# PROC010B_XDS110_Interface_1B.net
KiCad netlist of a schematic drawn in Altium Designer
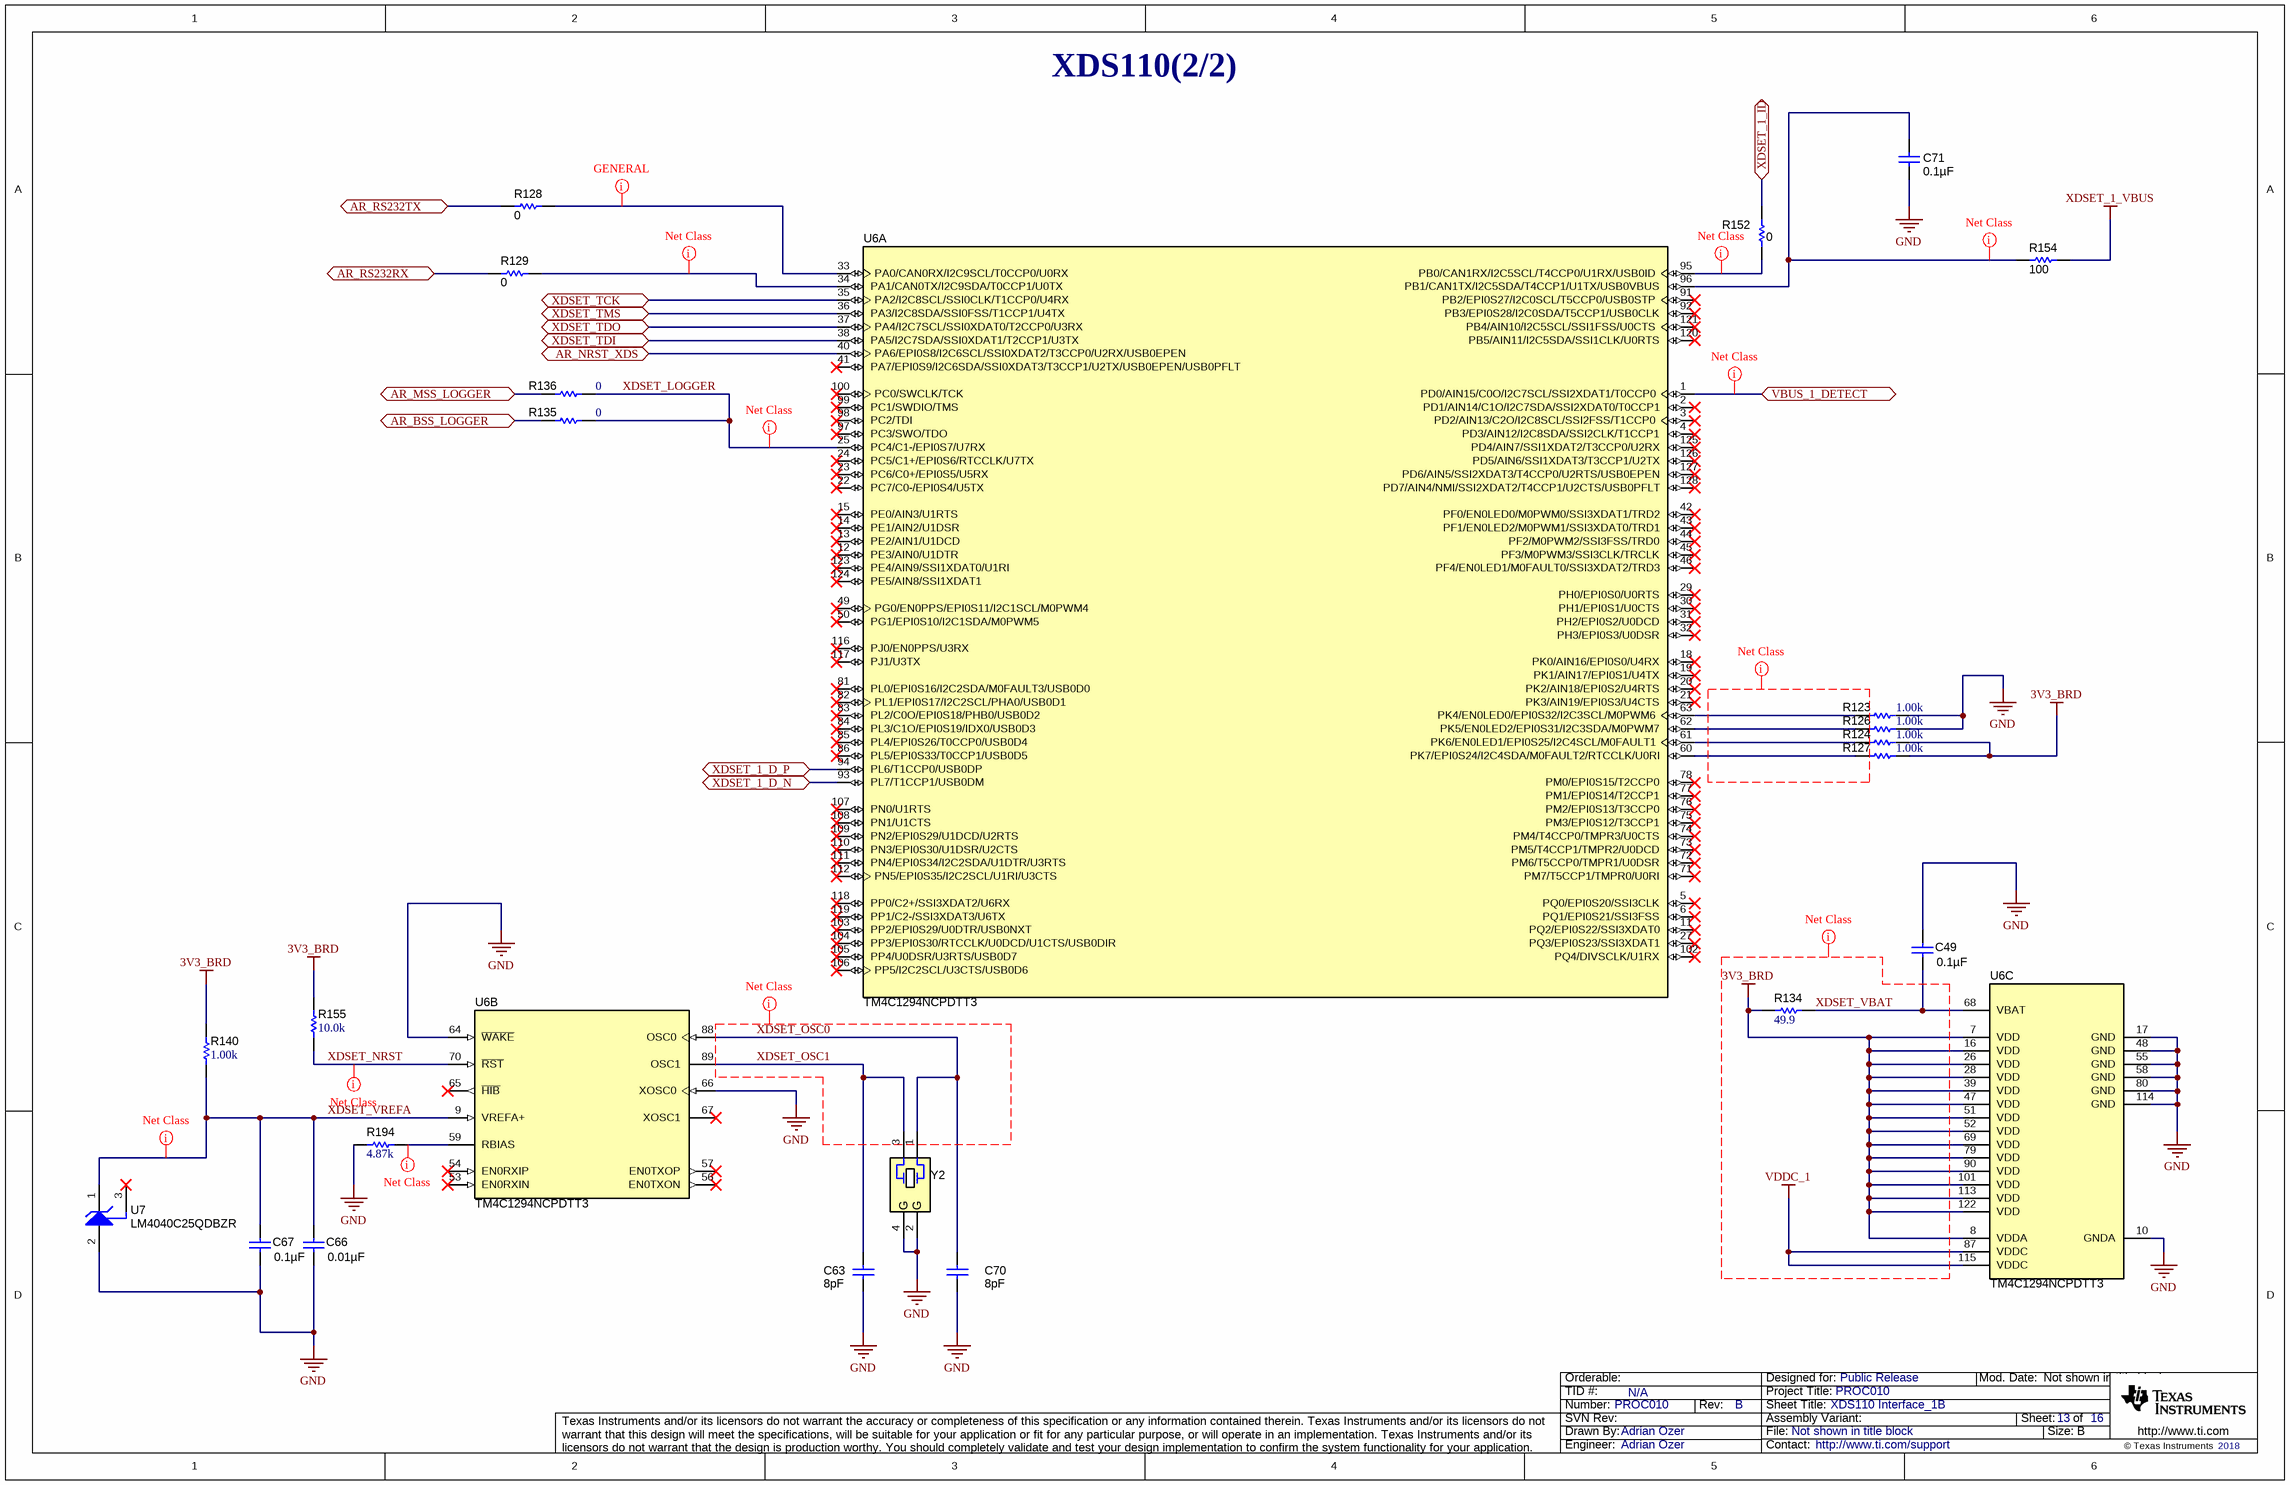
[diagram p0: PROC010B_XDS110 Interface_1B.SchDoc]

(export (version "E")
  (design (tool "Eeschema 10.0.6"))
  (components
    (comp (ref "C49")
      (value "C0402C104K8RACTU")
      (footprint "0402L")
      (description "CAP, CERM, 0.1 µF, 10 V,+/- 10%, X7R, 0402")
      (fields (field (name "MANUFACTURER") "Kemet") (field (name "VALUEDISPLAYED") "0.1µF"))
      (libsource (lib "Altium Vault - TI") (part "CMP-0078241-1"))
    )
    (comp (ref "C63")
      (value "GRM1555C1H8R0DA01D")
      (footprint "0402L")
      (description "CAP, CERM, 8 pF, 50 V, +/- 6%, C0G/NP0, 0402")
      (fields
        (field (name "MANUFACTURER") "MuRata")
        (field (name "VALUEDISPLAYED") "8pF")
        (field (name "PUBLISHER") "Texas Instruments")
      )
      (libsource (lib "Altium Vault - TI") (part "CMP-0006494-2"))
    )
    (comp (ref "C66")
      (value "C0402C103K4RACTU")
      (footprint "0402L")
      (description "CAP, CERM, 0.01 µF, 16 V,+/- 10%, X7R, 0402")
      (fields (field (name "MANUFACTURER") "Kemet") (field (name "VALUEDISPLAYED") "0.01µF"))
      (libsource (lib "Altium Vault - TI") (part "Capacitor"))
    )
    (comp (ref "C67")
      (value "C0402C104K8RACTU")
      (footprint "0402L")
      (description "CAP, CERM, 0.1 µF, 10 V,+/- 10%, X7R, 0402")
      (fields (field (name "MANUFACTURER") "Kemet") (field (name "VALUEDISPLAYED") "0.1µF"))
      (libsource (lib "Altium Vault - TI") (part "Capacitor"))
    )
    (comp (ref "C70")
      (value "GRM1555C1H8R0DA01D")
      (footprint "0402L")
      (description "CAP, CERM, 8 pF, 50 V, +/- 6%, C0G/NP0, 0402")
      (fields
        (field (name "MANUFACTURER") "MuRata")
        (field (name "VALUEDISPLAYED") "8pF")
        (field (name "PUBLISHER") "Texas Instruments")
      )
      (libsource (lib "Altium Vault - TI") (part "CMP-0006494-2"))
    )
    (comp (ref "C71")
      (value "C0402C104K8RACTU")
      (footprint "0402L")
      (description "CAP, CERM, 0.1 µF, 10 V,+/- 10%, X7R, 0402")
      (fields (field (name "MANUFACTURER") "Kemet") (field (name "VALUEDISPLAYED") "0.1µF"))
      (libsource (lib "Altium Vault - TI") (part "Capacitor"))
    )
    (comp (ref "R123")
      (value "CRCW04021K00FKED")
      (footprint "0402L")
      (description "RES, 1.00 k, 1%, 0.063 W, AEC-Q200 Grade 0, 0402")
      (fields (field (name "MANUFACTURER") "Vishay-Dale") (field (name "VALUEDISPLAYED") "1.00k"))
      (libsource (lib "Altium Vault - TI") (part "Resistor"))
    )
    (comp (ref "R124")
      (value "CRCW04021K00FKED")
      (footprint "0402L")
      (description "RES, 1.00 k, 1%, 0.063 W, AEC-Q200 Grade 0, 0402")
      (fields (field (name "MANUFACTURER") "Vishay-Dale") (field (name "VALUEDISPLAYED") "1.00k"))
      (libsource (lib "Altium Vault - TI") (part "Resistor"))
    )
    (comp (ref "R126")
      (value "CRCW04021K00FKED")
      (footprint "0402L")
      (description "RES, 1.00 k, 1%, 0.063 W, AEC-Q200 Grade 0, 0402")
      (fields (field (name "MANUFACTURER") "Vishay-Dale") (field (name "VALUEDISPLAYED") "1.00k"))
      (libsource (lib "Altium Vault - TI") (part "Resistor"))
    )
    (comp (ref "R127")
      (value "CRCW04021K00FKED")
      (footprint "0402L")
      (description "RES, 1.00 k, 1%, 0.063 W, AEC-Q200 Grade 0, 0402")
      (fields (field (name "MANUFACTURER") "Vishay-Dale") (field (name "VALUEDISPLAYED") "1.00k"))
      (libsource (lib "Altium Vault - TI") (part "Resistor"))
    )
    (comp (ref "R128")
      (value "ERJ-2GE0R00X")
      (footprint "0402L")
      (description "RES, 0, 5%, 0.063 W, 0402")
      (fields
        (field (name "MANUFACTURER") "Panasonic")
        (field (name "VALUEDISPLAYED") "0")
        (field (name "PUBLISHER") "Texas Instruments")
      )
      (libsource (lib "Altium Vault - TI") (part "Resistor"))
    )
    (comp (ref "R129")
      (value "ERJ-2GE0R00X")
      (footprint "0402L")
      (description "RES, 0, 5%, 0.063 W, 0402")
      (fields
        (field (name "MANUFACTURER") "Panasonic")
        (field (name "VALUEDISPLAYED") "0")
        (field (name "PUBLISHER") "Texas Instruments")
      )
      (libsource (lib "Altium Vault - TI") (part "Resistor"))
    )
    (comp (ref "R134")
      (value "CRCW040249R9FKED")
      (footprint "0402L")
      (description "RES, 49.9, 1%, 0.063 W, AEC-Q200 Grade 0, 0402")
      (fields (field (name "MANUFACTURER") "Vishay-Dale") (field (name "VALUEDISPLAYED") "49.9"))
      (libsource (lib "Altium Vault - TI") (part "Resistor"))
    )
    (comp (ref "R135")
      (value "CRCW02010000Z0ED")
      (footprint "0201_Silk")
      (description "RES, 0, 5%, 0.05 W, 0201")
      (fields (field (name "MANUFACTURER") "Vishay-Dale") (field (name "VALUEDISPLAYED") "0"))
      (libsource (lib "Altium Vault - TI") (part "Resistor"))
    )
    (comp (ref "R136")
      (value "CRCW02010000Z0ED")
      (footprint "0201_Silk")
      (description "RES, 0, 5%, 0.05 W, 0201")
      (fields (field (name "MANUFACTURER") "Vishay-Dale") (field (name "VALUEDISPLAYED") "0"))
      (libsource (lib "Altium Vault - TI") (part "Resistor"))
    )
    (comp (ref "R140")
      (value "CRCW04021K00FKED")
      (footprint "0402L")
      (description "RES, 1.00 k, 1%, 0.063 W, AEC-Q200 Grade 0, 0402")
      (fields (field (name "MANUFACTURER") "Vishay-Dale") (field (name "VALUEDISPLAYED") "1.00k"))
      (libsource (lib "Altium Vault - TI") (part "Resistor"))
    )
    (comp (ref "R152")
      (value "ERJ-2GE0R00X")
      (footprint "0402L")
      (description "RES, 0, 5%, 0.063 W, 0402")
      (fields
        (field (name "MANUFACTURER") "Panasonic")
        (field (name "VALUEDISPLAYED") "0")
        (field (name "PUBLISHER") "Texas Instruments")
      )
      (libsource (lib "Altium Vault - TI") (part "Resistor"))
    )
    (comp (ref "R154")
      (value "ERJ-2GEJ101X")
      (footprint "0402L")
      (description "RES, 100, 5%, 0.1 W, AEC-Q200 Grade 0, 0402")
      (fields
        (field (name "MANUFACTURER") "Panasonic")
        (field (name "VALUEDISPLAYED") "100")
        (field (name "PUBLISHER") "Texas Instruments")
      )
      (libsource (lib "Altium Vault - TI") (part "Resistor"))
    )
    (comp (ref "R155")
      (value "CRCW040210K0FKED")
      (footprint "0402L")
      (description "RES, 10.0 k, 1%, 0.063 W, AEC-Q200 Grade 0, 0402")
      (fields (field (name "MANUFACTURER") "Vishay-Dale") (field (name "VALUEDISPLAYED") "10.0k"))
      (libsource (lib "Altium Vault - TI") (part "Resistor"))
    )
    (comp (ref "R194")
      (value "CRCW04024K87FKED")
      (footprint "0402L")
      (description "RES, 4.87 k, 1%, 0.063 W, AEC-Q200 Grade 0, 0402")
      (fields (field (name "MANUFACTURER") "Vishay-Dale") (field (name "VALUEDISPLAYED") "4.87k"))
      (libsource (lib "Altium Vault - TI") (part "Resistor"))
    )
    (comp (ref "U6")
      (value "TM4C1294NCPDTT3")
      (footprint "PDT0128A")
      (fields (field (name "PARTNUMBER") "TM4C1294NCPDTT3") (field (name "MANUFACTURER") "Texas Instruments"))
      (libsource (lib "Altium Vault - TI") (part "TI-TM4C1294NCPDT-128"))
    )
    (comp (ref "U7")
      (value "LM4040C25QDBZR")
      (footprint "DBZ0003A_N")
      (fields (field (name "MANUFACTURER") "Texas Instruments") (field (name "PARTNUMBER") "LM4040C25QDBZR"))
      (libsource (lib "Altium Vault - TI") (part "TI-LM4040C25DBZ3"))
    )
    (comp (ref "Y2")
      (value "NX3225SA-16.000M-STD-CRS-2")
      (footprint "NDK_NX3225SA")
      (description "Crystal, 16 MHz, 15 ppm, 8 pF, AEC-Q200 Grade 1, SMD")
      (fields (field (name "MANUFACTURER") "NDK"))
      (libsource (lib "Altium Vault - TI") (part "CMP-0078214-2"))
    )
  )
  (nets
    (net (code "1") (name "/AR_BSS_LOGGER") (class "Default")
      (node (ref "R135") (pin "1") (pinfunction "1_1") (pintype "passive"))
    )
    (net (code "2") (name "/AR_MSS_LOGGER") (class "Default")
      (node (ref "R136") (pin "1") (pinfunction "1_1") (pintype "passive"))
    )
    (net (code "3") (name "/AR_NRST_XDS") (class "Default")
      (node (ref "U6") (pin "40") (pinfunction "PA6/EPI0S8/I2C6SCL/SSI0XDAT2/T3CCP0/U2RX/USB0EPEN_40") (pintype "bidirectional"))
    )
    (net (code "4") (name "/AR_RS232RX") (class "Default")
      (node (ref "R129") (pin "1") (pinfunction "1_1") (pintype "passive"))
    )
    (net (code "5") (name "/AR_RS232TX") (class "Default")
      (node (ref "R128") (pin "1") (pinfunction "1_1") (pintype "passive"))
    )
    (net (code "6") (name "/VBUS_1_DETECT") (class "Default")
      (node (ref "U6") (pin "1") (pinfunction "PD0/AIN15/C0O/I2C7SCL/SSI2XDAT1/T0CCP0_1") (pintype "bidirectional"))
    )
    (net (code "7") (name "/XDSET_1_D_N") (class "Default")
      (node (ref "U6") (pin "93") (pinfunction "PL7/T1CCP1/USB0DM_93") (pintype "bidirectional"))
    )
    (net (code "8") (name "/XDSET_1_D_P") (class "Default")
      (node (ref "U6") (pin "94") (pinfunction "PL6/T1CCP0/USB0DP_94") (pintype "bidirectional"))
    )
    (net (code "9") (name "/XDSET_1_ID") (class "Default")
      (node (ref "R152") (pin "2") (pinfunction "2_2") (pintype "passive"))
    )
    (net (code "10") (name "/XDSET_LOGGER") (class "Default")
      (node (ref "R135") (pin "2") (pinfunction "2_2") (pintype "passive"))
      (node (ref "R136") (pin "2") (pinfunction "2_2") (pintype "passive"))
      (node (ref "U6") (pin "25") (pinfunction "PC4/C1-/EPI0S7/U7RX_25") (pintype "bidirectional"))
    )
    (net (code "11") (name "/XDSET_NRST") (class "Default")
      (node (ref "R155") (pin "1") (pinfunction "1_1") (pintype "passive"))
      (node (ref "U6") (pin "70") (pinfunction "~{RST}_70") (pintype "input"))
    )
    (net (code "12") (name "/XDSET_OSC0") (class "Default")
      (node (ref "C70") (pin "2") (pinfunction "2_2") (pintype "passive"))
      (node (ref "U6") (pin "88") (pinfunction "OSC0_88") (pintype "input"))
      (node (ref "Y2") (pin "1") (pinfunction "1_1") (pintype "passive"))
    )
    (net (code "13") (name "/XDSET_OSC1") (class "Default")
      (node (ref "C63") (pin "2") (pinfunction "2_2") (pintype "passive"))
      (node (ref "U6") (pin "89") (pinfunction "OSC1_89") (pintype "passive"))
      (node (ref "Y2") (pin "3") (pinfunction "3_3") (pintype "passive"))
    )
    (net (code "14") (name "/XDSET_TCK") (class "Default")
      (node (ref "U6") (pin "35") (pinfunction "PA2/I2C8SCL/SSI0CLK/T1CCP0/U4RX_35") (pintype "bidirectional"))
    )
    (net (code "15") (name "/XDSET_TDI") (class "Default")
      (node (ref "U6") (pin "38") (pinfunction "PA5/I2C7SDA/SSI0XDAT1/T2CCP1/U3TX_38") (pintype "bidirectional"))
    )
    (net (code "16") (name "/XDSET_TDO") (class "Default")
      (node (ref "U6") (pin "37") (pinfunction "PA4/I2C7SCL/SSI0XDAT0/T2CCP0/U3RX_37") (pintype "bidirectional"))
    )
    (net (code "17") (name "/XDSET_TMS") (class "Default")
      (node (ref "U6") (pin "36") (pinfunction "PA3/I2C8SDA/SSI0FSS/T1CCP1/U4TX_36") (pintype "bidirectional"))
    )
    (net (code "18") (name "/XDSET_VBAT") (class "Default")
      (node (ref "C49") (pin "2") (pinfunction "2_2") (pintype "passive"))
      (node (ref "R134") (pin "1") (pinfunction "1_1") (pintype "passive"))
      (node (ref "U6") (pin "68") (pinfunction "VBAT_68") (pintype "power_in"))
    )
    (net (code "19") (name "/XDSET_VREFA") (class "Default")
      (node (ref "C66") (pin "2") (pinfunction "2_2") (pintype "passive"))
      (node (ref "C67") (pin "2") (pinfunction "2_2") (pintype "passive"))
      (node (ref "R140") (pin "1") (pinfunction "1_1") (pintype "passive"))
      (node (ref "U6") (pin "9") (pinfunction "VREFA+_9") (pintype "input"))
      (node (ref "U7") (pin "1") (pinfunction "CATHODE_1") (pintype "passive"))
    )
    (net (code "20") (name "3V3_BRD") (class "Default")
      (node (ref "R124") (pin "2") (pinfunction "2_2") (pintype "passive"))
      (node (ref "R127") (pin "2") (pinfunction "2_2") (pintype "passive"))
      (node (ref "R134") (pin "2") (pinfunction "2_2") (pintype "passive"))
      (node (ref "R140") (pin "2") (pinfunction "2_2") (pintype "passive"))
      (node (ref "R155") (pin "2") (pinfunction "2_2") (pintype "passive"))
      (node (ref "U6") (pin "101") (pinfunction "VDD_101") (pintype "power_in"))
      (node (ref "U6") (pin "113") (pinfunction "VDD_113") (pintype "power_in"))
      (node (ref "U6") (pin "122") (pinfunction "VDD_122") (pintype "power_in"))
      (node (ref "U6") (pin "16") (pinfunction "VDD_16") (pintype "power_in"))
      (node (ref "U6") (pin "26") (pinfunction "VDD_26") (pintype "power_in"))
      (node (ref "U6") (pin "28") (pinfunction "VDD_28") (pintype "power_in"))
      (node (ref "U6") (pin "39") (pinfunction "VDD_39") (pintype "power_in"))
      (node (ref "U6") (pin "47") (pinfunction "VDD_47") (pintype "power_in"))
      (node (ref "U6") (pin "51") (pinfunction "VDD_51") (pintype "power_in"))
      (node (ref "U6") (pin "52") (pinfunction "VDD_52") (pintype "power_in"))
      (node (ref "U6") (pin "69") (pinfunction "VDD_69") (pintype "power_in"))
      (node (ref "U6") (pin "7") (pinfunction "VDD_7") (pintype "power_in"))
      (node (ref "U6") (pin "79") (pinfunction "VDD_79") (pintype "power_in"))
      (node (ref "U6") (pin "8") (pinfunction "VDDA_8") (pintype "power_in"))
      (node (ref "U6") (pin "90") (pinfunction "VDD_90") (pintype "power_in"))
    )
    (net (code "21") (name "GND") (class "Default")
      (node (ref "C49") (pin "1") (pinfunction "1_1") (pintype "passive"))
      (node (ref "C63") (pin "1") (pinfunction "1_1") (pintype "passive"))
      (node (ref "C66") (pin "1") (pinfunction "1_1") (pintype "passive"))
      (node (ref "C67") (pin "1") (pinfunction "1_1") (pintype "passive"))
      (node (ref "C70") (pin "1") (pinfunction "1_1") (pintype "passive"))
      (node (ref "C71") (pin "1") (pinfunction "1_1") (pintype "passive"))
      (node (ref "R123") (pin "2") (pinfunction "2_2") (pintype "passive"))
      (node (ref "R126") (pin "2") (pinfunction "2_2") (pintype "passive"))
      (node (ref "R194") (pin "1") (pinfunction "1_1") (pintype "passive"))
      (node (ref "U6") (pin "10") (pinfunction "GNDA_10") (pintype "power_in"))
      (node (ref "U6") (pin "114") (pinfunction "GND_114") (pintype "power_in"))
      (node (ref "U6") (pin "17") (pinfunction "GND_17") (pintype "power_in"))
      (node (ref "U6") (pin "48") (pinfunction "GND_48") (pintype "power_in"))
      (node (ref "U6") (pin "55") (pinfunction "GND_55") (pintype "power_in"))
      (node (ref "U6") (pin "58") (pinfunction "GND_58") (pintype "power_in"))
      (node (ref "U6") (pin "64") (pinfunction "~{WAKE}_64") (pintype "input"))
      (node (ref "U6") (pin "66") (pinfunction "XOSC0_66") (pintype "input"))
      (node (ref "U6") (pin "80") (pinfunction "GND_80") (pintype "power_in"))
      (node (ref "U7") (pin "2") (pinfunction "ANODE_2") (pintype "passive"))
      (node (ref "Y2") (pin "2") (pinfunction "GND_2") (pintype "power_in"))
      (node (ref "Y2") (pin "4") (pinfunction "GND_4") (pintype "power_in"))
    )
    (net (code "22") (name "Net-(U6A-PA0{slash}CAN0RX{slash}I2C9SCL{slash}T0CCP0{slash}U0RX)") (class "Default")
      (node (ref "R128") (pin "2") (pinfunction "2_2") (pintype "passive"))
      (node (ref "U6") (pin "33") (pinfunction "PA0/CAN0RX/I2C9SCL/T0CCP0/U0RX_33") (pintype "bidirectional"))
    )
    (net (code "23") (name "Net-(U6A-PA1{slash}CAN0TX{slash}I2C9SDA{slash}T0CCP1{slash}U0TX)") (class "Default")
      (node (ref "R129") (pin "2") (pinfunction "2_2") (pintype "passive"))
      (node (ref "U6") (pin "34") (pinfunction "PA1/CAN0TX/I2C9SDA/T0CCP1/U0TX_34") (pintype "bidirectional"))
    )
    (net (code "24") (name "Net-(U6A-PB0{slash}CAN1RX{slash}I2C5SCL{slash}T4CCP0{slash}U1RX{slash}USB0ID)") (class "Default")
      (node (ref "R152") (pin "1") (pinfunction "1_1") (pintype "passive"))
      (node (ref "U6") (pin "95") (pinfunction "PB0/CAN1RX/I2C5SCL/T4CCP0/U1RX/USB0ID_95") (pintype "bidirectional"))
    )
    (net (code "25") (name "Net-(U6A-PB1{slash}CAN1TX{slash}I2C5SDA{slash}T4CCP1{slash}U1TX{slash}USB0VBUS)") (class "Default")
      (node (ref "C71") (pin "2") (pinfunction "2_2") (pintype "passive"))
      (node (ref "R154") (pin "1") (pinfunction "1_1") (pintype "passive"))
      (node (ref "U6") (pin "96") (pinfunction "PB1/CAN1TX/I2C5SDA/T4CCP1/U1TX/USB0VBUS_96") (pintype "bidirectional"))
    )
    (net (code "26") (name "Net-(U6A-PK4{slash}EN0LED0{slash}EPI0S32{slash}I2C3SCL{slash}M0PWM6)") (class "Default")
      (node (ref "R123") (pin "1") (pinfunction "1_1") (pintype "passive"))
      (node (ref "U6") (pin "63") (pinfunction "PK4/EN0LED0/EPI0S32/I2C3SCL/M0PWM6_63") (pintype "bidirectional"))
    )
    (net (code "27") (name "Net-(U6A-PK5{slash}EN0LED2{slash}EPI0S31{slash}I2C3SDA{slash}M0PWM7)") (class "Default")
      (node (ref "R126") (pin "1") (pinfunction "1_1") (pintype "passive"))
      (node (ref "U6") (pin "62") (pinfunction "PK5/EN0LED2/EPI0S31/I2C3SDA/M0PWM7_62") (pintype "bidirectional"))
    )
    (net (code "28") (name "Net-(U6A-PK6{slash}EN0LED1{slash}EPI0S25{slash}I2C4SCL{slash}M0FAULT1)") (class "Default")
      (node (ref "R124") (pin "1") (pinfunction "1_1") (pintype "passive"))
      (node (ref "U6") (pin "61") (pinfunction "PK6/EN0LED1/EPI0S25/I2C4SCL/M0FAULT1_61") (pintype "bidirectional"))
    )
    (net (code "29") (name "Net-(U6A-PK7{slash}EPI0S24{slash}I2C4SDA{slash}M0FAULT2{slash}RTCCLK{slash}U0RI)") (class "Default")
      (node (ref "R127") (pin "1") (pinfunction "1_1") (pintype "passive"))
      (node (ref "U6") (pin "60") (pinfunction "PK7/EPI0S24/I2C4SDA/M0FAULT2/RTCCLK/U0RI_60") (pintype "bidirectional"))
    )
    (net (code "30") (name "Net-(U6B-RBIAS)") (class "Default")
      (node (ref "R194") (pin "2") (pinfunction "2_2") (pintype "passive"))
      (node (ref "U6") (pin "59") (pinfunction "RBIAS_59") (pintype "passive"))
    )
    (net (code "31") (name "VDDC_1") (class "Default")
      (node (ref "U6") (pin "115") (pinfunction "VDDC_115") (pintype "power_in"))
      (node (ref "U6") (pin "87") (pinfunction "VDDC_87") (pintype "power_in"))
    )
    (net (code "32") (name "XDSET_1_VBUS") (class "Default")
      (node (ref "R154") (pin "2") (pinfunction "2_2") (pintype "passive"))
    )
    (net (code "33") (name "unconnected-(U6A-PA7{slash}EPI0S9{slash}I2C6SDA{slash}SSI0XDAT3{slash}T3CCP1{slash}U2TX{slash}USB0EPEN{slash}USB0PFLT-Pad41)") (class "Default")
      (node (ref "U6") (pin "41") (pinfunction "PA7/EPI0S9/I2C6SDA/SSI0XDAT3/T3CCP1/U2TX/USB0EPEN/USB0PFLT_41") (pintype "bidirectional+no_connect"))
    )
    (net (code "34") (name "unconnected-(U6A-PB2{slash}EPI0S27{slash}I2C0SCL{slash}T5CCP0{slash}USB0STP-Pad91)") (class "Default")
      (node (ref "U6") (pin "91") (pinfunction "PB2/EPI0S27/I2C0SCL/T5CCP0/USB0STP_91") (pintype "bidirectional+no_connect"))
    )
    (net (code "35") (name "unconnected-(U6A-PB3{slash}EPI0S28{slash}I2C0SDA{slash}T5CCP1{slash}USB0CLK-Pad92)") (class "Default")
      (node (ref "U6") (pin "92") (pinfunction "PB3/EPI0S28/I2C0SDA/T5CCP1/USB0CLK_92") (pintype "bidirectional+no_connect"))
    )
    (net (code "36") (name "unconnected-(U6A-PB4{slash}AIN10{slash}I2C5SCL{slash}SSI1FSS{slash}U0CTS-Pad121)") (class "Default")
      (node (ref "U6") (pin "121") (pinfunction "PB4/AIN10/I2C5SCL/SSI1FSS/U0CTS_121") (pintype "bidirectional+no_connect"))
    )
    (net (code "37") (name "unconnected-(U6A-PB5{slash}AIN11{slash}I2C5SDA{slash}SSI1CLK{slash}U0RTS-Pad120)") (class "Default")
      (node (ref "U6") (pin "120") (pinfunction "PB5/AIN11/I2C5SDA/SSI1CLK/U0RTS_120") (pintype "bidirectional+no_connect"))
    )
    (net (code "38") (name "unconnected-(U6A-PC0{slash}SWCLK{slash}TCK-Pad100)") (class "Default")
      (node (ref "U6") (pin "100") (pinfunction "PC0/SWCLK/TCK_100") (pintype "bidirectional+no_connect"))
    )
    (net (code "39") (name "unconnected-(U6A-PC1{slash}SWDIO{slash}TMS-Pad99)") (class "Default")
      (node (ref "U6") (pin "99") (pinfunction "PC1/SWDIO/TMS_99") (pintype "bidirectional+no_connect"))
    )
    (net (code "40") (name "unconnected-(U6A-PC2{slash}TDI-Pad98)") (class "Default")
      (node (ref "U6") (pin "98") (pinfunction "PC2/TDI_98") (pintype "bidirectional+no_connect"))
    )
    (net (code "41") (name "unconnected-(U6A-PC3{slash}SWO{slash}TDO-Pad97)") (class "Default")
      (node (ref "U6") (pin "97") (pinfunction "PC3/SWO/TDO_97") (pintype "bidirectional+no_connect"))
    )
    (net (code "42") (name "unconnected-(U6A-PC5{slash}C1+{slash}EPI0S6{slash}RTCCLK{slash}U7TX-Pad24)") (class "Default")
      (node (ref "U6") (pin "24") (pinfunction "PC5/C1+/EPI0S6/RTCCLK/U7TX_24") (pintype "bidirectional+no_connect"))
    )
    (net (code "43") (name "unconnected-(U6A-PC6{slash}C0+{slash}EPI0S5{slash}U5RX-Pad23)") (class "Default")
      (node (ref "U6") (pin "23") (pinfunction "PC6/C0+/EPI0S5/U5RX_23") (pintype "bidirectional+no_connect"))
    )
    (net (code "44") (name "unconnected-(U6A-PC7{slash}C0-{slash}EPI0S4{slash}U5TX-Pad22)") (class "Default")
      (node (ref "U6") (pin "22") (pinfunction "PC7/C0-/EPI0S4/U5TX_22") (pintype "bidirectional+no_connect"))
    )
    (net (code "45") (name "unconnected-(U6A-PD1{slash}AIN14{slash}C1O{slash}I2C7SDA{slash}SSI2XDAT0{slash}T0CCP1-Pad2)") (class "Default")
      (node (ref "U6") (pin "2") (pinfunction "PD1/AIN14/C1O/I2C7SDA/SSI2XDAT0/T0CCP1_2") (pintype "bidirectional+no_connect"))
    )
    (net (code "46") (name "unconnected-(U6A-PD2{slash}AIN13{slash}C2O{slash}I2C8SCL{slash}SSI2FSS{slash}T1CCP0-Pad3)") (class "Default")
      (node (ref "U6") (pin "3") (pinfunction "PD2/AIN13/C2O/I2C8SCL/SSI2FSS/T1CCP0_3") (pintype "bidirectional+no_connect"))
    )
    (net (code "47") (name "unconnected-(U6A-PD3{slash}AIN12{slash}I2C8SDA{slash}SSI2CLK{slash}T1CCP1-Pad4)") (class "Default")
      (node (ref "U6") (pin "4") (pinfunction "PD3/AIN12/I2C8SDA/SSI2CLK/T1CCP1_4") (pintype "bidirectional+no_connect"))
    )
    (net (code "48") (name "unconnected-(U6A-PD4{slash}AIN7{slash}SSI1XDAT2{slash}T3CCP0{slash}U2RX-Pad125)") (class "Default")
      (node (ref "U6") (pin "125") (pinfunction "PD4/AIN7/SSI1XDAT2/T3CCP0/U2RX_125") (pintype "bidirectional+no_connect"))
    )
    (net (code "49") (name "unconnected-(U6A-PD5{slash}AIN6{slash}SSI1XDAT3{slash}T3CCP1{slash}U2TX-Pad126)") (class "Default")
      (node (ref "U6") (pin "126") (pinfunction "PD5/AIN6/SSI1XDAT3/T3CCP1/U2TX_126") (pintype "bidirectional+no_connect"))
    )
    (net (code "50") (name "unconnected-(U6A-PD6{slash}AIN5{slash}SSI2XDAT3{slash}T4CCP0{slash}U2RTS{slash}USB0EPEN-Pad127)") (class "Default")
      (node (ref "U6") (pin "127") (pinfunction "PD6/AIN5/SSI2XDAT3/T4CCP0/U2RTS/USB0EPEN_127") (pintype "bidirectional+no_connect"))
    )
    (net (code "51") (name "unconnected-(U6A-PD7{slash}AIN4{slash}NMI{slash}SSI2XDAT2{slash}T4CCP1{slash}U2CTS{slash}USB0PFLT-Pad128)") (class "Default")
      (node (ref "U6") (pin "128") (pinfunction "PD7/AIN4/NMI/SSI2XDAT2/T4CCP1/U2CTS/USB0PFLT_128") (pintype "bidirectional+no_connect"))
    )
    (net (code "52") (name "unconnected-(U6A-PE0{slash}AIN3{slash}U1RTS-Pad15)") (class "Default")
      (node (ref "U6") (pin "15") (pinfunction "PE0/AIN3/U1RTS_15") (pintype "bidirectional+no_connect"))
    )
    (net (code "53") (name "unconnected-(U6A-PE1{slash}AIN2{slash}U1DSR-Pad14)") (class "Default")
      (node (ref "U6") (pin "14") (pinfunction "PE1/AIN2/U1DSR_14") (pintype "bidirectional+no_connect"))
    )
    (net (code "54") (name "unconnected-(U6A-PE2{slash}AIN1{slash}U1DCD-Pad13)") (class "Default")
      (node (ref "U6") (pin "13") (pinfunction "PE2/AIN1/U1DCD_13") (pintype "bidirectional+no_connect"))
    )
    (net (code "55") (name "unconnected-(U6A-PE3{slash}AIN0{slash}U1DTR-Pad12)") (class "Default")
      (node (ref "U6") (pin "12") (pinfunction "PE3/AIN0/U1DTR_12") (pintype "bidirectional+no_connect"))
    )
    (net (code "56") (name "unconnected-(U6A-PE4{slash}AIN9{slash}SSI1XDAT0{slash}U1RI-Pad123)") (class "Default")
      (node (ref "U6") (pin "123") (pinfunction "PE4/AIN9/SSI1XDAT0/U1RI_123") (pintype "bidirectional+no_connect"))
    )
    (net (code "57") (name "unconnected-(U6A-PE5{slash}AIN8{slash}SSI1XDAT1-Pad124)") (class "Default")
      (node (ref "U6") (pin "124") (pinfunction "PE5/AIN8/SSI1XDAT1_124") (pintype "bidirectional+no_connect"))
    )
    (net (code "58") (name "unconnected-(U6A-PF0{slash}EN0LED0{slash}M0PWM0{slash}SSI3XDAT1{slash}TRD2-Pad42)") (class "Default")
      (node (ref "U6") (pin "42") (pinfunction "PF0/EN0LED0/M0PWM0/SSI3XDAT1/TRD2_42") (pintype "bidirectional+no_connect"))
    )
    (net (code "59") (name "unconnected-(U6A-PF1{slash}EN0LED2{slash}M0PWM1{slash}SSI3XDAT0{slash}TRD1-Pad43)") (class "Default")
      (node (ref "U6") (pin "43") (pinfunction "PF1/EN0LED2/M0PWM1/SSI3XDAT0/TRD1_43") (pintype "bidirectional+no_connect"))
    )
    (net (code "60") (name "unconnected-(U6A-PF2{slash}M0PWM2{slash}SSI3FSS{slash}TRD0-Pad44)") (class "Default")
      (node (ref "U6") (pin "44") (pinfunction "PF2/M0PWM2/SSI3FSS/TRD0_44") (pintype "bidirectional+no_connect"))
    )
    (net (code "61") (name "unconnected-(U6A-PF3{slash}M0PWM3{slash}SSI3CLK{slash}TRCLK-Pad45)") (class "Default")
      (node (ref "U6") (pin "45") (pinfunction "PF3/M0PWM3/SSI3CLK/TRCLK_45") (pintype "bidirectional+no_connect"))
    )
    (net (code "62") (name "unconnected-(U6A-PF4{slash}EN0LED1{slash}M0FAULT0{slash}SSI3XDAT2{slash}TRD3-Pad46)") (class "Default")
      (node (ref "U6") (pin "46") (pinfunction "PF4/EN0LED1/M0FAULT0/SSI3XDAT2/TRD3_46") (pintype "bidirectional+no_connect"))
    )
    (net (code "63") (name "unconnected-(U6A-PG0{slash}EN0PPS{slash}EPI0S11{slash}I2C1SCL{slash}M0PWM4-Pad49)") (class "Default")
      (node (ref "U6") (pin "49") (pinfunction "PG0/EN0PPS/EPI0S11/I2C1SCL/M0PWM4_49") (pintype "bidirectional+no_connect"))
    )
    (net (code "64") (name "unconnected-(U6A-PG1{slash}EPI0S10{slash}I2C1SDA{slash}M0PWM5-Pad50)") (class "Default")
      (node (ref "U6") (pin "50") (pinfunction "PG1/EPI0S10/I2C1SDA/M0PWM5_50") (pintype "bidirectional+no_connect"))
    )
    (net (code "65") (name "unconnected-(U6A-PH0{slash}EPI0S0{slash}U0RTS-Pad29)") (class "Default")
      (node (ref "U6") (pin "29") (pinfunction "PH0/EPI0S0/U0RTS_29") (pintype "bidirectional+no_connect"))
    )
    (net (code "66") (name "unconnected-(U6A-PH1{slash}EPI0S1{slash}U0CTS-Pad30)") (class "Default")
      (node (ref "U6") (pin "30") (pinfunction "PH1/EPI0S1/U0CTS_30") (pintype "bidirectional+no_connect"))
    )
    (net (code "67") (name "unconnected-(U6A-PH2{slash}EPI0S2{slash}U0DCD-Pad31)") (class "Default")
      (node (ref "U6") (pin "31") (pinfunction "PH2/EPI0S2/U0DCD_31") (pintype "bidirectional+no_connect"))
    )
    (net (code "68") (name "unconnected-(U6A-PH3{slash}EPI0S3{slash}U0DSR-Pad32)") (class "Default")
      (node (ref "U6") (pin "32") (pinfunction "PH3/EPI0S3/U0DSR_32") (pintype "bidirectional+no_connect"))
    )
    (net (code "69") (name "unconnected-(U6A-PJ0{slash}EN0PPS{slash}U3RX-Pad116)") (class "Default")
      (node (ref "U6") (pin "116") (pinfunction "PJ0/EN0PPS/U3RX_116") (pintype "bidirectional+no_connect"))
    )
    (net (code "70") (name "unconnected-(U6A-PJ1{slash}U3TX-Pad117)") (class "Default")
      (node (ref "U6") (pin "117") (pinfunction "PJ1/U3TX_117") (pintype "bidirectional+no_connect"))
    )
    (net (code "71") (name "unconnected-(U6A-PK0{slash}AIN16{slash}EPI0S0{slash}U4RX-Pad18)") (class "Default")
      (node (ref "U6") (pin "18") (pinfunction "PK0/AIN16/EPI0S0/U4RX_18") (pintype "bidirectional+no_connect"))
    )
    (net (code "72") (name "unconnected-(U6A-PK1{slash}AIN17{slash}EPI0S1{slash}U4TX-Pad19)") (class "Default")
      (node (ref "U6") (pin "19") (pinfunction "PK1/AIN17/EPI0S1/U4TX_19") (pintype "bidirectional+no_connect"))
    )
    (net (code "73") (name "unconnected-(U6A-PK2{slash}AIN18{slash}EPI0S2{slash}U4RTS-Pad20)") (class "Default")
      (node (ref "U6") (pin "20") (pinfunction "PK2/AIN18/EPI0S2/U4RTS_20") (pintype "bidirectional+no_connect"))
    )
    (net (code "74") (name "unconnected-(U6A-PK3{slash}AIN19{slash}EPI0S3{slash}U4CTS-Pad21)") (class "Default")
      (node (ref "U6") (pin "21") (pinfunction "PK3/AIN19/EPI0S3/U4CTS_21") (pintype "bidirectional+no_connect"))
    )
    (net (code "75") (name "unconnected-(U6A-PL0{slash}EPI0S16{slash}I2C2SDA{slash}M0FAULT3{slash}USB0D0-Pad81)") (class "Default")
      (node (ref "U6") (pin "81") (pinfunction "PL0/EPI0S16/I2C2SDA/M0FAULT3/USB0D0_81") (pintype "bidirectional+no_connect"))
    )
    (net (code "76") (name "unconnected-(U6A-PL1{slash}EPI0S17{slash}I2C2SCL{slash}PHA0{slash}USB0D1-Pad82)") (class "Default")
      (node (ref "U6") (pin "82") (pinfunction "PL1/EPI0S17/I2C2SCL/PHA0/USB0D1_82") (pintype "bidirectional+no_connect"))
    )
    (net (code "77") (name "unconnected-(U6A-PL2{slash}C0O{slash}EPI0S18{slash}PHB0{slash}USB0D2-Pad83)") (class "Default")
      (node (ref "U6") (pin "83") (pinfunction "PL2/C0O/EPI0S18/PHB0/USB0D2_83") (pintype "bidirectional+no_connect"))
    )
    (net (code "78") (name "unconnected-(U6A-PL3{slash}C1O{slash}EPI0S19{slash}IDX0{slash}USB0D3-Pad84)") (class "Default")
      (node (ref "U6") (pin "84") (pinfunction "PL3/C1O/EPI0S19/IDX0/USB0D3_84") (pintype "bidirectional+no_connect"))
    )
    (net (code "79") (name "unconnected-(U6A-PL4{slash}EPI0S26{slash}T0CCP0{slash}USB0D4-Pad85)") (class "Default")
      (node (ref "U6") (pin "85") (pinfunction "PL4/EPI0S26/T0CCP0/USB0D4_85") (pintype "bidirectional+no_connect"))
    )
    (net (code "80") (name "unconnected-(U6A-PL5{slash}EPI0S33{slash}T0CCP1{slash}USB0D5-Pad86)") (class "Default")
      (node (ref "U6") (pin "86") (pinfunction "PL5/EPI0S33/T0CCP1/USB0D5_86") (pintype "bidirectional+no_connect"))
    )
    (net (code "81") (name "unconnected-(U6A-PM0{slash}EPI0S15{slash}T2CCP0-Pad78)") (class "Default")
      (node (ref "U6") (pin "78") (pinfunction "PM0/EPI0S15/T2CCP0_78") (pintype "bidirectional+no_connect"))
    )
    (net (code "82") (name "unconnected-(U6A-PM1{slash}EPI0S14{slash}T2CCP1-Pad77)") (class "Default")
      (node (ref "U6") (pin "77") (pinfunction "PM1/EPI0S14/T2CCP1_77") (pintype "bidirectional+no_connect"))
    )
    (net (code "83") (name "unconnected-(U6A-PM2{slash}EPI0S13{slash}T3CCP0-Pad76)") (class "Default")
      (node (ref "U6") (pin "76") (pinfunction "PM2/EPI0S13/T3CCP0_76") (pintype "bidirectional+no_connect"))
    )
    (net (code "84") (name "unconnected-(U6A-PM3{slash}EPI0S12{slash}T3CCP1-Pad75)") (class "Default")
      (node (ref "U6") (pin "75") (pinfunction "PM3/EPI0S12/T3CCP1_75") (pintype "bidirectional+no_connect"))
    )
    (net (code "85") (name "unconnected-(U6A-PM4{slash}T4CCP0{slash}TMPR3{slash}U0CTS-Pad74)") (class "Default")
      (node (ref "U6") (pin "74") (pinfunction "PM4/T4CCP0/TMPR3/U0CTS_74") (pintype "bidirectional+no_connect"))
    )
    (net (code "86") (name "unconnected-(U6A-PM5{slash}T4CCP1{slash}TMPR2{slash}U0DCD-Pad73)") (class "Default")
      (node (ref "U6") (pin "73") (pinfunction "PM5/T4CCP1/TMPR2/U0DCD_73") (pintype "bidirectional+no_connect"))
    )
    (net (code "87") (name "unconnected-(U6A-PM6{slash}T5CCP0{slash}TMPR1{slash}U0DSR-Pad72)") (class "Default")
      (node (ref "U6") (pin "72") (pinfunction "PM6/T5CCP0/TMPR1/U0DSR_72") (pintype "bidirectional+no_connect"))
    )
    (net (code "88") (name "unconnected-(U6A-PM7{slash}T5CCP1{slash}TMPR0{slash}U0RI-Pad71)") (class "Default")
      (node (ref "U6") (pin "71") (pinfunction "PM7/T5CCP1/TMPR0/U0RI_71") (pintype "bidirectional+no_connect"))
    )
    (net (code "89") (name "unconnected-(U6A-PN0{slash}U1RTS-Pad107)") (class "Default")
      (node (ref "U6") (pin "107") (pinfunction "PN0/U1RTS_107") (pintype "bidirectional+no_connect"))
    )
    (net (code "90") (name "unconnected-(U6A-PN1{slash}U1CTS-Pad108)") (class "Default")
      (node (ref "U6") (pin "108") (pinfunction "PN1/U1CTS_108") (pintype "bidirectional+no_connect"))
    )
    (net (code "91") (name "unconnected-(U6A-PN2{slash}EPI0S29{slash}U1DCD{slash}U2RTS-Pad109)") (class "Default")
      (node (ref "U6") (pin "109") (pinfunction "PN2/EPI0S29/U1DCD/U2RTS_109") (pintype "bidirectional+no_connect"))
    )
    (net (code "92") (name "unconnected-(U6A-PN3{slash}EPI0S30{slash}U1DSR{slash}U2CTS-Pad110)") (class "Default")
      (node (ref "U6") (pin "110") (pinfunction "PN3/EPI0S30/U1DSR/U2CTS_110") (pintype "bidirectional+no_connect"))
    )
    (net (code "93") (name "unconnected-(U6A-PN4{slash}EPI0S34{slash}I2C2SDA{slash}U1DTR{slash}U3RTS-Pad111)") (class "Default")
      (node (ref "U6") (pin "111") (pinfunction "PN4/EPI0S34/I2C2SDA/U1DTR/U3RTS_111") (pintype "bidirectional+no_connect"))
    )
    (net (code "94") (name "unconnected-(U6A-PN5{slash}EPI0S35{slash}I2C2SCL{slash}U1RI{slash}U3CTS-Pad112)") (class "Default")
      (node (ref "U6") (pin "112") (pinfunction "PN5/EPI0S35/I2C2SCL/U1RI/U3CTS_112") (pintype "bidirectional+no_connect"))
    )
    (net (code "95") (name "unconnected-(U6A-PP0{slash}C2+{slash}SSI3XDAT2{slash}U6RX-Pad118)") (class "Default")
      (node (ref "U6") (pin "118") (pinfunction "PP0/C2+/SSI3XDAT2/U6RX_118") (pintype "bidirectional+no_connect"))
    )
    (net (code "96") (name "unconnected-(U6A-PP1{slash}C2-{slash}SSI3XDAT3{slash}U6TX-Pad119)") (class "Default")
      (node (ref "U6") (pin "119") (pinfunction "PP1/C2-/SSI3XDAT3/U6TX_119") (pintype "bidirectional+no_connect"))
    )
    (net (code "97") (name "unconnected-(U6A-PP2{slash}EPI0S29{slash}U0DTR{slash}USB0NXT-Pad103)") (class "Default")
      (node (ref "U6") (pin "103") (pinfunction "PP2/EPI0S29/U0DTR/USB0NXT_103") (pintype "bidirectional+no_connect"))
    )
    (net (code "98") (name "unconnected-(U6A-PP3{slash}EPI0S30{slash}RTCCLK{slash}U0DCD{slash}U1CTS{slash}USB0DIR-Pad104)") (class "Default")
      (node (ref "U6") (pin "104") (pinfunction "PP3/EPI0S30/RTCCLK/U0DCD/U1CTS/USB0DIR_104") (pintype "bidirectional+no_connect"))
    )
    (net (code "99") (name "unconnected-(U6A-PP4{slash}U0DSR{slash}U3RTS{slash}USB0D7-Pad105)") (class "Default")
      (node (ref "U6") (pin "105") (pinfunction "PP4/U0DSR/U3RTS/USB0D7_105") (pintype "bidirectional+no_connect"))
    )
    (net (code "100") (name "unconnected-(U6A-PP5{slash}I2C2SCL{slash}U3CTS{slash}USB0D6-Pad106)") (class "Default")
      (node (ref "U6") (pin "106") (pinfunction "PP5/I2C2SCL/U3CTS/USB0D6_106") (pintype "bidirectional+no_connect"))
    )
    (net (code "101") (name "unconnected-(U6A-PQ0{slash}EPI0S20{slash}SSI3CLK-Pad5)") (class "Default")
      (node (ref "U6") (pin "5") (pinfunction "PQ0/EPI0S20/SSI3CLK_5") (pintype "bidirectional+no_connect"))
    )
    (net (code "102") (name "unconnected-(U6A-PQ1{slash}EPI0S21{slash}SSI3FSS-Pad6)") (class "Default")
      (node (ref "U6") (pin "6") (pinfunction "PQ1/EPI0S21/SSI3FSS_6") (pintype "bidirectional+no_connect"))
    )
    (net (code "103") (name "unconnected-(U6A-PQ2{slash}EPI0S22{slash}SSI3XDAT0-Pad11)") (class "Default")
      (node (ref "U6") (pin "11") (pinfunction "PQ2/EPI0S22/SSI3XDAT0_11") (pintype "bidirectional+no_connect"))
    )
    (net (code "104") (name "unconnected-(U6A-PQ3{slash}EPI0S23{slash}SSI3XDAT1-Pad27)") (class "Default")
      (node (ref "U6") (pin "27") (pinfunction "PQ3/EPI0S23/SSI3XDAT1_27") (pintype "bidirectional+no_connect"))
    )
    (net (code "105") (name "unconnected-(U6A-PQ4{slash}DIVSCLK{slash}U1RX-Pad102)") (class "Default")
      (node (ref "U6") (pin "102") (pinfunction "PQ4/DIVSCLK/U1RX_102") (pintype "bidirectional+no_connect"))
    )
    (net (code "106") (name "unconnected-(U6B-EN0RXIN-Pad53)") (class "Default")
      (node (ref "U6") (pin "53") (pinfunction "EN0RXIN_53") (pintype "input+no_connect"))
    )
    (net (code "107") (name "unconnected-(U6B-EN0RXIP-Pad54)") (class "Default")
      (node (ref "U6") (pin "54") (pinfunction "EN0RXIP_54") (pintype "input+no_connect"))
    )
    (net (code "108") (name "unconnected-(U6B-EN0TXON-Pad56)") (class "Default")
      (node (ref "U6") (pin "56") (pinfunction "EN0TXON_56") (pintype "output+no_connect"))
    )
    (net (code "109") (name "unconnected-(U6B-EN0TXOP-Pad57)") (class "Default")
      (node (ref "U6") (pin "57") (pinfunction "EN0TXOP_57") (pintype "output+no_connect"))
    )
    (net (code "110") (name "unconnected-(U6B-XOSC1-Pad67)") (class "Default")
      (node (ref "U6") (pin "67") (pinfunction "XOSC1_67") (pintype "passive+no_connect"))
    )
    (net (code "111") (name "unconnected-(U6B-~{HIB}-Pad65)") (class "Default")
      (node (ref "U6") (pin "65") (pinfunction "~{HIB}_65") (pintype "output+no_connect"))
    )
    (net (code "112") (name "unconnected-(U7-NC-Pad3)") (class "Default")
      (node (ref "U7") (pin "3") (pinfunction "NC_3") (pintype "passive+no_connect"))
    )
  )
)
